# scarab-trigger-shield.net
KiCad netlist of a schematic drawn in EAGLE
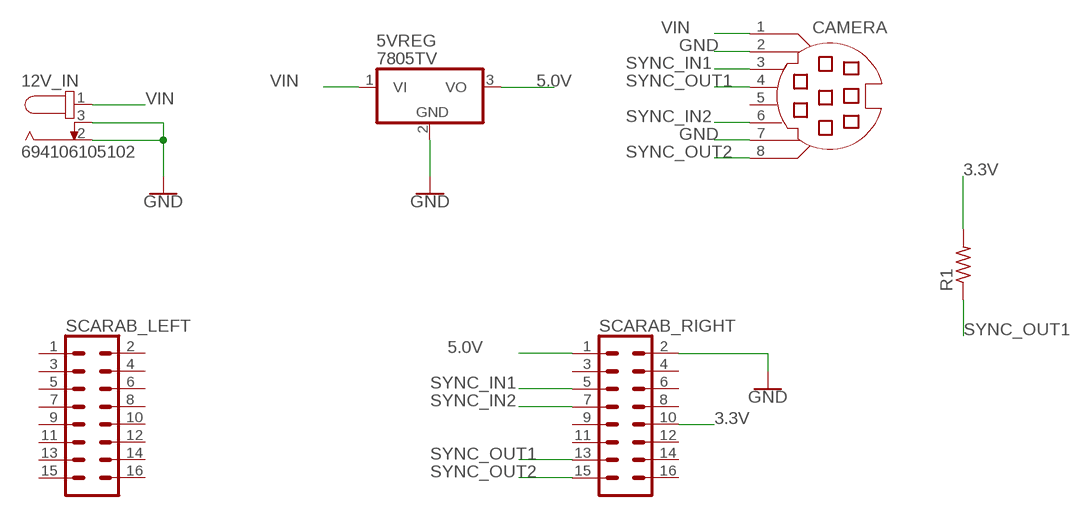
[diagram p0: schematic, sheet 1]

(export (version "E")
  (design (tool "Eeschema 10.0.6"))
  (components
    (comp (ref "5VREG")
      (value "7805TV")
      (footprint "eagle-import:TO220V")
      (libsource (lib "eagle-import") (part "78TV05"))
    )
    (comp (ref "12V_IN")
      (value "694106105102")
      (footprint "eagle-import:694106105102")
      (libsource (lib "eagle-import") (part "694106105102"))
    )
    (comp (ref "CAMERA")
      (value "MD08SS")
      (footprint "eagle-import:MDIN08SS")
      (libsource (lib "eagle-import") (part "MD08SS"))
    )
    (comp (ref "R1")
      (value "R-US_M1206")
      (footprint "eagle-import:M1206")
      (libsource (lib "eagle-import") (part "R-US_M1206"))
    )
    (comp (ref "SCARAB_LEFT")
      (value "CONN_08X2")
      (footprint "eagle-import:2X8")
      (libsource (lib "eagle-import") (part "CONN_08X2"))
    )
    (comp (ref "SCARAB_RIGHT")
      (value "CONN_08X2")
      (footprint "eagle-import:2X8")
      (libsource (lib "eagle-import") (part "CONN_08X2"))
    )
  )
  (nets
    (net (code "1") (name "/3.3V") (class "Default")
      (node (ref "R1") (pin "2") (pinfunction "2_2") (pintype "passive"))
      (node (ref "SCARAB_RIGHT") (pin "10") (pinfunction "10_10") (pintype "passive"))
    )
    (net (code "2") (name "/5.0V") (class "Default")
      (node (ref "5VREG") (pin "3") (pinfunction "VO_3") (pintype "passive"))
      (node (ref "SCARAB_RIGHT") (pin "1") (pinfunction "1_1") (pintype "passive"))
    )
    (net (code "3") (name "/SYNC_IN1") (class "Default")
      (node (ref "CAMERA") (pin "3") (pinfunction "3_3") (pintype "passive"))
      (node (ref "SCARAB_RIGHT") (pin "5") (pinfunction "5_5") (pintype "passive"))
    )
    (net (code "4") (name "/SYNC_IN2") (class "Default")
      (node (ref "CAMERA") (pin "6") (pinfunction "6_6") (pintype "passive"))
      (node (ref "SCARAB_RIGHT") (pin "7") (pinfunction "7_7") (pintype "passive"))
    )
    (net (code "5") (name "/SYNC_OUT1") (class "Default")
      (node (ref "CAMERA") (pin "4") (pinfunction "4_4") (pintype "passive"))
      (node (ref "R1") (pin "1") (pinfunction "1_1") (pintype "passive"))
      (node (ref "SCARAB_RIGHT") (pin "13") (pinfunction "13_13") (pintype "passive"))
    )
    (net (code "6") (name "/SYNC_OUT2") (class "Default")
      (node (ref "CAMERA") (pin "8") (pinfunction "8_8") (pintype "passive"))
      (node (ref "SCARAB_RIGHT") (pin "15") (pinfunction "15_15") (pintype "passive"))
    )
    (net (code "7") (name "/VIN") (class "Default")
      (node (ref "12V_IN") (pin "1") (pinfunction "1_1") (pintype "passive"))
      (node (ref "5VREG") (pin "1") (pinfunction "VI_1") (pintype "input"))
      (node (ref "CAMERA") (pin "1") (pinfunction "1_1") (pintype "passive"))
    )
    (net (code "8") (name "GND") (class "Default")
      (node (ref "12V_IN") (pin "2") (pinfunction "2_2") (pintype "passive"))
      (node (ref "12V_IN") (pin "3") (pinfunction "3_3") (pintype "passive"))
      (node (ref "5VREG") (pin "2") (pinfunction "GND_2") (pintype "passive"))
      (node (ref "CAMERA") (pin "2") (pinfunction "2_2") (pintype "passive"))
      (node (ref "CAMERA") (pin "7") (pinfunction "7_7") (pintype "passive"))
      (node (ref "SCARAB_RIGHT") (pin "2") (pinfunction "2_2") (pintype "passive"))
    )
    (net (code "9") (name "unconnected-(CAMERA-Pad5)") (class "Default")
      (node (ref "CAMERA") (pin "5") (pinfunction "5_5") (pintype "passive"))
    )
    (net (code "10") (name "unconnected-(SCARAB_LEFT-Pad1)") (class "Default")
      (node (ref "SCARAB_LEFT") (pin "1") (pinfunction "1_1") (pintype "passive"))
    )
    (net (code "11") (name "unconnected-(SCARAB_LEFT-Pad2)") (class "Default")
      (node (ref "SCARAB_LEFT") (pin "2") (pinfunction "2_2") (pintype "passive"))
    )
    (net (code "12") (name "unconnected-(SCARAB_LEFT-Pad3)") (class "Default")
      (node (ref "SCARAB_LEFT") (pin "3") (pinfunction "3_3") (pintype "passive"))
    )
    (net (code "13") (name "unconnected-(SCARAB_LEFT-Pad4)") (class "Default")
      (node (ref "SCARAB_LEFT") (pin "4") (pinfunction "4_4") (pintype "passive"))
    )
    (net (code "14") (name "unconnected-(SCARAB_LEFT-Pad5)") (class "Default")
      (node (ref "SCARAB_LEFT") (pin "5") (pinfunction "5_5") (pintype "passive"))
    )
    (net (code "15") (name "unconnected-(SCARAB_LEFT-Pad6)") (class "Default")
      (node (ref "SCARAB_LEFT") (pin "6") (pinfunction "6_6") (pintype "passive"))
    )
    (net (code "16") (name "unconnected-(SCARAB_LEFT-Pad7)") (class "Default")
      (node (ref "SCARAB_LEFT") (pin "7") (pinfunction "7_7") (pintype "passive"))
    )
    (net (code "17") (name "unconnected-(SCARAB_LEFT-Pad8)") (class "Default")
      (node (ref "SCARAB_LEFT") (pin "8") (pinfunction "8_8") (pintype "passive"))
    )
    (net (code "18") (name "unconnected-(SCARAB_LEFT-Pad9)") (class "Default")
      (node (ref "SCARAB_LEFT") (pin "9") (pinfunction "9_9") (pintype "passive"))
    )
    (net (code "19") (name "unconnected-(SCARAB_LEFT-Pad10)") (class "Default")
      (node (ref "SCARAB_LEFT") (pin "10") (pinfunction "10_10") (pintype "passive"))
    )
    (net (code "20") (name "unconnected-(SCARAB_LEFT-Pad11)") (class "Default")
      (node (ref "SCARAB_LEFT") (pin "11") (pinfunction "11_11") (pintype "passive"))
    )
    (net (code "21") (name "unconnected-(SCARAB_LEFT-Pad12)") (class "Default")
      (node (ref "SCARAB_LEFT") (pin "12") (pinfunction "12_12") (pintype "passive"))
    )
    (net (code "22") (name "unconnected-(SCARAB_LEFT-Pad13)") (class "Default")
      (node (ref "SCARAB_LEFT") (pin "13") (pinfunction "13_13") (pintype "passive"))
    )
    (net (code "23") (name "unconnected-(SCARAB_LEFT-Pad14)") (class "Default")
      (node (ref "SCARAB_LEFT") (pin "14") (pinfunction "14_14") (pintype "passive"))
    )
    (net (code "24") (name "unconnected-(SCARAB_LEFT-Pad15)") (class "Default")
      (node (ref "SCARAB_LEFT") (pin "15") (pinfunction "15_15") (pintype "passive"))
    )
    (net (code "25") (name "unconnected-(SCARAB_LEFT-Pad16)") (class "Default")
      (node (ref "SCARAB_LEFT") (pin "16") (pinfunction "16_16") (pintype "passive"))
    )
    (net (code "26") (name "unconnected-(SCARAB_RIGHT-Pad3)") (class "Default")
      (node (ref "SCARAB_RIGHT") (pin "3") (pinfunction "3_3") (pintype "passive"))
    )
    (net (code "27") (name "unconnected-(SCARAB_RIGHT-Pad4)") (class "Default")
      (node (ref "SCARAB_RIGHT") (pin "4") (pinfunction "4_4") (pintype "passive"))
    )
    (net (code "28") (name "unconnected-(SCARAB_RIGHT-Pad6)") (class "Default")
      (node (ref "SCARAB_RIGHT") (pin "6") (pinfunction "6_6") (pintype "passive"))
    )
    (net (code "29") (name "unconnected-(SCARAB_RIGHT-Pad8)") (class "Default")
      (node (ref "SCARAB_RIGHT") (pin "8") (pinfunction "8_8") (pintype "passive"))
    )
    (net (code "30") (name "unconnected-(SCARAB_RIGHT-Pad9)") (class "Default")
      (node (ref "SCARAB_RIGHT") (pin "9") (pinfunction "9_9") (pintype "passive"))
    )
    (net (code "31") (name "unconnected-(SCARAB_RIGHT-Pad11)") (class "Default")
      (node (ref "SCARAB_RIGHT") (pin "11") (pinfunction "11_11") (pintype "passive"))
    )
    (net (code "32") (name "unconnected-(SCARAB_RIGHT-Pad12)") (class "Default")
      (node (ref "SCARAB_RIGHT") (pin "12") (pinfunction "12_12") (pintype "passive"))
    )
    (net (code "33") (name "unconnected-(SCARAB_RIGHT-Pad14)") (class "Default")
      (node (ref "SCARAB_RIGHT") (pin "14") (pinfunction "14_14") (pintype "passive"))
    )
    (net (code "34") (name "unconnected-(SCARAB_RIGHT-Pad16)") (class "Default")
      (node (ref "SCARAB_RIGHT") (pin "16") (pinfunction "16_16") (pintype "passive"))
    )
  )
)
